# PSU.net
KiCad netlist of a schematic drawn in EAGLE
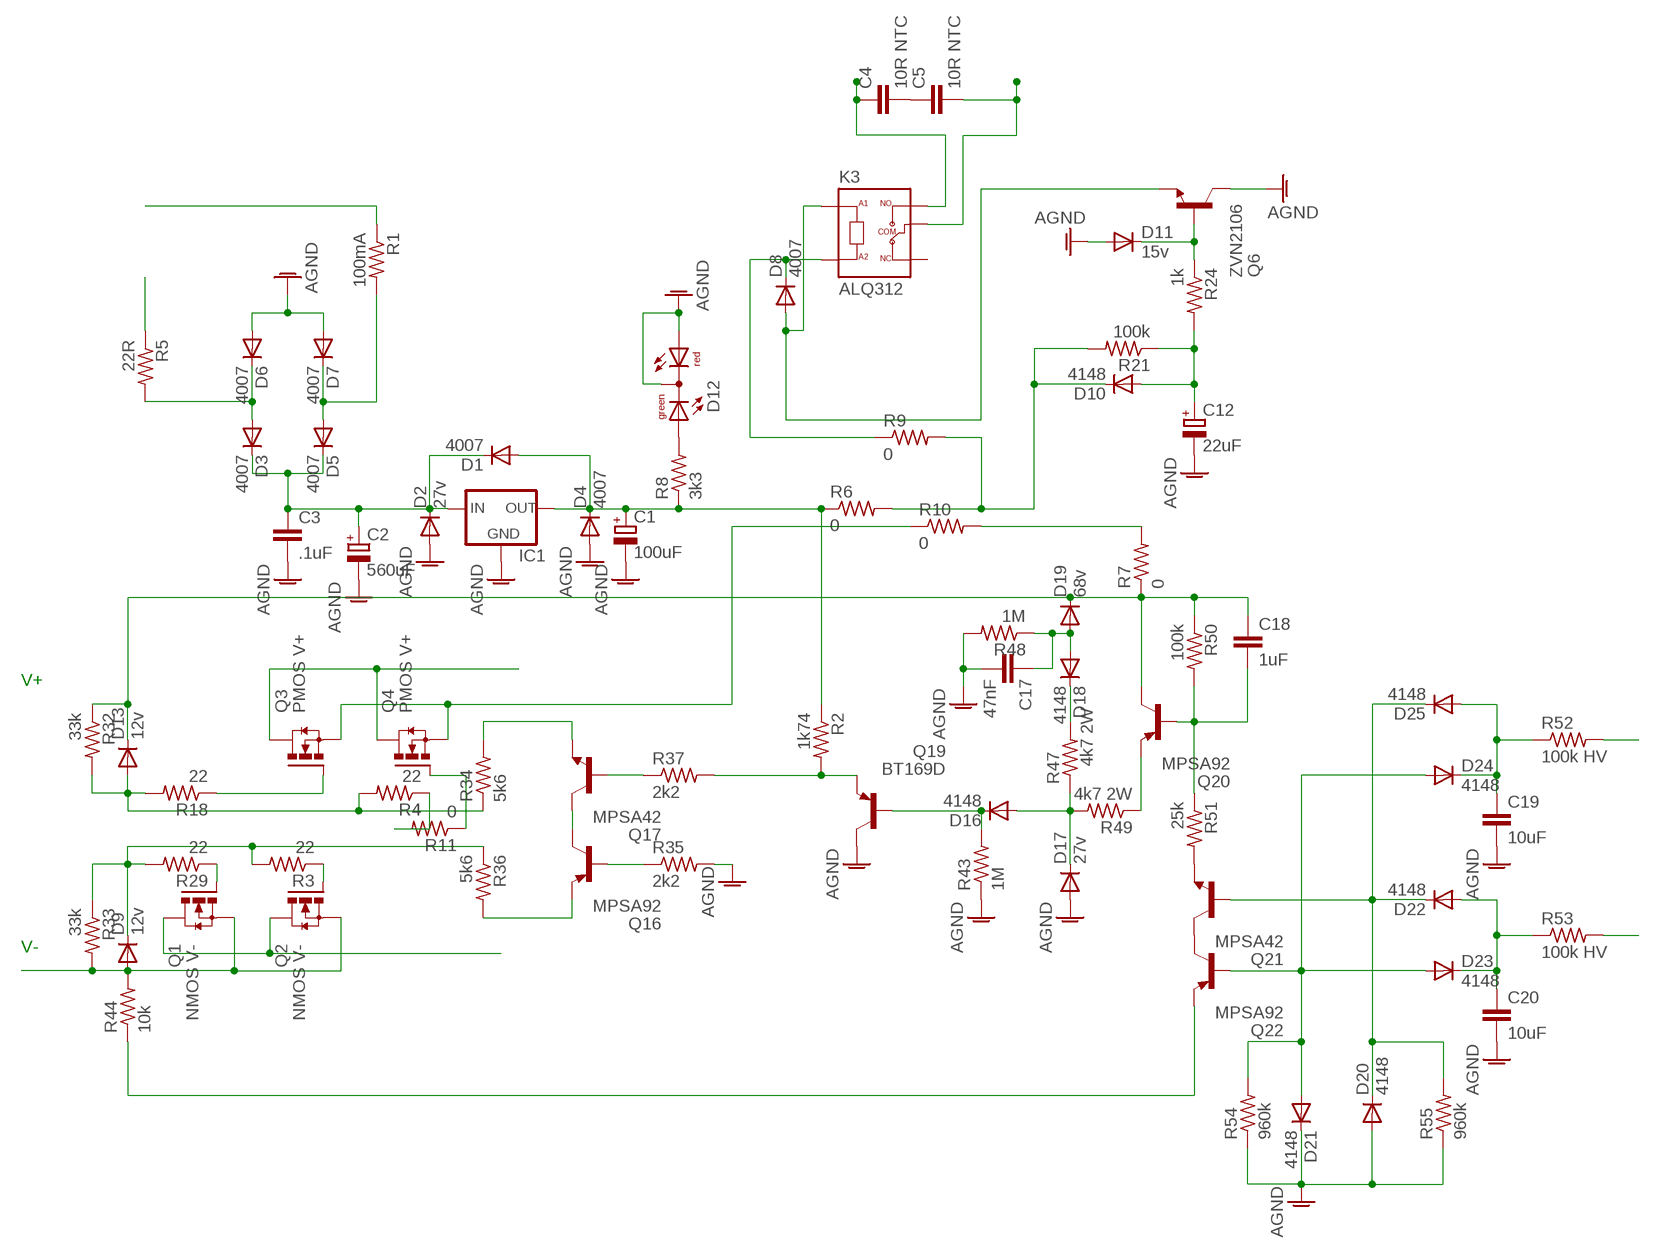
[diagram p0: schematic, sheet 1]

(export (version "E")
  (design (tool "Eeschema 10.0.6"))
  (components
    (comp (ref "C1")
      (value "100uF")
      (footprint "eagle-import:E3,5-10")
      (libsource (lib "eagle-import") (part "CPOL-EUE3.5-10"))
    )
    (comp (ref "C2")
      (value "560uF")
      (footprint "eagle-import:E5-13")
      (libsource (lib "eagle-import") (part "CPOL-EUE5-13"))
    )
    (comp (ref "C3")
      (value ".1uF")
      (footprint "eagle-import:C075-032X103")
      (libsource (lib "eagle-import") (part "C-EU075-032X103"))
    )
    (comp (ref "C4")
      (value "10R NTC")
      (footprint "eagle-import:C075-063X106")
      (libsource (lib "eagle-import") (part "C-EU075-063X106"))
    )
    (comp (ref "C5")
      (value "10R NTC")
      (footprint "eagle-import:C075-063X106")
      (libsource (lib "eagle-import") (part "C-EU075-063X106"))
    )
    (comp (ref "C12")
      (value "22uF")
      (footprint "eagle-import:E2,5-7")
      (libsource (lib "eagle-import") (part "CPOL-EUE2.5-7"))
    )
    (comp (ref "C17")
      (value "47nF")
      (footprint "eagle-import:C050-035X075")
      (libsource (lib "eagle-import") (part "C-EU050-035X075"))
    )
    (comp (ref "C18")
      (value "1uF")
      (footprint "eagle-import:C050-035X075")
      (libsource (lib "eagle-import") (part "C-EU050-035X075"))
    )
    (comp (ref "C19")
      (value "10uF")
      (footprint "eagle-import:C050-075X075")
      (libsource (lib "eagle-import") (part "C-EU050-075X075"))
    )
    (comp (ref "C20")
      (value "10uF")
      (footprint "eagle-import:C050-075X075")
      (libsource (lib "eagle-import") (part "C-EU050-075X075"))
    )
    (comp (ref "D1")
      (value "4007")
      (footprint "eagle-import:DO41-10")
      (libsource (lib "eagle-import") (part "1N4004"))
    )
    (comp (ref "D2")
      (value "27v")
      (footprint "eagle-import:DO41-10")
      (libsource (lib "eagle-import") (part "1N4004"))
    )
    (comp (ref "D3")
      (value "4007")
      (footprint "eagle-import:DO41-10")
      (libsource (lib "eagle-import") (part "1N4004"))
    )
    (comp (ref "D4")
      (value "4007")
      (footprint "eagle-import:DO41-10")
      (libsource (lib "eagle-import") (part "1N4004"))
    )
    (comp (ref "D5")
      (value "4007")
      (footprint "eagle-import:DO41-10")
      (libsource (lib "eagle-import") (part "1N4004"))
    )
    (comp (ref "D6")
      (value "4007")
      (footprint "eagle-import:DO41-10")
      (libsource (lib "eagle-import") (part "1N4004"))
    )
    (comp (ref "D7")
      (value "4007")
      (footprint "eagle-import:DO41-10")
      (libsource (lib "eagle-import") (part "1N4004"))
    )
    (comp (ref "D8")
      (value "4007")
      (footprint "eagle-import:DO41-10")
      (libsource (lib "eagle-import") (part "1N4004"))
    )
    (comp (ref "D9")
      (value "12v")
      (footprint "eagle-import:DO41-10")
      (libsource (lib "eagle-import") (part "1N4004"))
    )
    (comp (ref "D10")
      (value "4148")
      (footprint "eagle-import:DO35-10")
      (libsource (lib "eagle-import") (part "1N4148DO35-10"))
    )
    (comp (ref "D11")
      (value "15v")
      (footprint "eagle-import:DO35-7")
      (libsource (lib "eagle-import") (part "1N4148DO35-7"))
    )
    (comp (ref "D12")
      (value "DUOLED5MM")
      (footprint "eagle-import:DUOLED5MM")
      (libsource (lib "eagle-import") (part "DUOLED5MM"))
    )
    (comp (ref "D13")
      (value "12v")
      (footprint "eagle-import:DO41-10")
      (libsource (lib "eagle-import") (part "1N4004"))
    )
    (comp (ref "D16")
      (value "4148")
      (footprint "eagle-import:DO41-10")
      (libsource (lib "eagle-import") (part "1N4004"))
    )
    (comp (ref "D17")
      (value "27v")
      (footprint "eagle-import:DO41-10")
      (libsource (lib "eagle-import") (part "1N4004"))
    )
    (comp (ref "D18")
      (value "4148")
      (footprint "eagle-import:DO41-10")
      (libsource (lib "eagle-import") (part "1N4004"))
    )
    (comp (ref "D19")
      (value "68v")
      (footprint "eagle-import:DO41-10")
      (libsource (lib "eagle-import") (part "1N4004"))
    )
    (comp (ref "D20")
      (value "4148")
      (footprint "eagle-import:DO35-7")
      (libsource (lib "eagle-import") (part "1N4148DO35-7"))
    )
    (comp (ref "D21")
      (value "4148")
      (footprint "eagle-import:DO35-7")
      (libsource (lib "eagle-import") (part "1N4148DO35-7"))
    )
    (comp (ref "D22")
      (value "4148")
      (footprint "eagle-import:DO35-7")
      (libsource (lib "eagle-import") (part "1N4148DO35-7"))
    )
    (comp (ref "D23")
      (value "4148")
      (footprint "eagle-import:DO35-7")
      (libsource (lib "eagle-import") (part "1N4148DO35-7"))
    )
    (comp (ref "D24")
      (value "4148")
      (footprint "eagle-import:DO35-7")
      (libsource (lib "eagle-import") (part "1N4148DO35-7"))
    )
    (comp (ref "D25")
      (value "4148")
      (footprint "eagle-import:DO35-7")
      (libsource (lib "eagle-import") (part "1N4148DO35-7"))
    )
    (comp (ref "IC1")
      (value "78XXS")
      (footprint "eagle-import:78XXS")
      (libsource (lib "eagle-import") (part "78XXS"))
    )
    (comp (ref "K3")
      (value "ALQ312")
      (footprint "eagle-import:RELAY_ALQ112")
      (fields (field (name "MF") "Panasonic Electric") (field (name "MP") "ALQ112"))
      (libsource (lib "eagle-import") (part "ALQ112"))
    )
    (comp (ref "Q1")
      (value "NMOS V-")
      (footprint "eagle-import:TO247BV")
      (libsource (lib "eagle-import") (part "IRFP240"))
    )
    (comp (ref "Q2")
      (value "NMOS V-")
      (footprint "eagle-import:TO247BV")
      (libsource (lib "eagle-import") (part "IRFP240"))
    )
    (comp (ref "Q3")
      (value "PMOS V+")
      (footprint "eagle-import:TO247BV")
      (libsource (lib "eagle-import") (part "IRFP240"))
    )
    (comp (ref "Q4")
      (value "PMOS V+")
      (footprint "eagle-import:TO247BV")
      (libsource (lib "eagle-import") (part "IRFP240"))
    )
    (comp (ref "Q6")
      (value "ZVN2106")
      (footprint "eagle-import:TO92-EBC")
      (libsource (lib "eagle-import") (part "BC550B"))
    )
    (comp (ref "Q16")
      (value "MPSA92")
      (footprint "eagle-import:TO92-EBC")
      (libsource (lib "eagle-import") (part "BC560"))
    )
    (comp (ref "Q17")
      (value "MPSA42")
      (footprint "eagle-import:TO92-EBC")
      (libsource (lib "eagle-import") (part "BC550B"))
    )
    (comp (ref "Q19")
      (value "BT169D")
      (footprint "eagle-import:TO92-EBC")
      (libsource (lib "eagle-import") (part "BC560"))
    )
    (comp (ref "Q20")
      (value "MPSA92")
      (footprint "eagle-import:TO92-EBC")
      (libsource (lib "eagle-import") (part "BC560"))
    )
    (comp (ref "Q21")
      (value "MPSA42")
      (footprint "eagle-import:TO92-EBC")
      (libsource (lib "eagle-import") (part "BC550B"))
    )
    (comp (ref "Q22")
      (value "MPSA92")
      (footprint "eagle-import:TO92-EBC")
      (libsource (lib "eagle-import") (part "BC560"))
    )
    (comp (ref "R1")
      (value "100mA")
      (footprint "eagle-import:0207_5V")
      (libsource (lib "eagle-import") (part "R-US_0207/5V"))
    )
    (comp (ref "R2")
      (value "1k74")
      (footprint "eagle-import:0309_10")
      (libsource (lib "eagle-import") (part "R-US_0309/10"))
    )
    (comp (ref "R3")
      (value "22")
      (footprint "eagle-import:0309_12")
      (libsource (lib "eagle-import") (part "R-US_0309/12"))
    )
    (comp (ref "R4")
      (value "22")
      (footprint "eagle-import:0309_12")
      (libsource (lib "eagle-import") (part "R-US_0309/12"))
    )
    (comp (ref "R5")
      (value "22R")
      (footprint "eagle-import:0309_12")
      (libsource (lib "eagle-import") (part "R-US_0309/12"))
    )
    (comp (ref "R6")
      (value "0")
      (footprint "eagle-import:0309_12")
      (libsource (lib "eagle-import") (part "R-US_0309/12"))
    )
    (comp (ref "R7")
      (value "0")
      (footprint "eagle-import:0309_12")
      (libsource (lib "eagle-import") (part "R-US_0309/12"))
    )
    (comp (ref "R8")
      (value "3k3")
      (footprint "eagle-import:0309_10")
      (libsource (lib "eagle-import") (part "R-US_0309/10"))
    )
    (comp (ref "R9")
      (value "0")
      (footprint "eagle-import:0309_10")
      (libsource (lib "eagle-import") (part "R-US_0309/10"))
    )
    (comp (ref "R10")
      (value "0")
      (footprint "eagle-import:0309_12")
      (libsource (lib "eagle-import") (part "R-US_0309/12"))
    )
    (comp (ref "R11")
      (value "0")
      (footprint "eagle-import:0309_12")
      (libsource (lib "eagle-import") (part "R-US_0309/12"))
    )
    (comp (ref "R18")
      (value "22")
      (footprint "eagle-import:0207_15")
      (libsource (lib "eagle-import") (part "R-US_0207/15"))
    )
    (comp (ref "R21")
      (value "100k")
      (footprint "eagle-import:0309_10")
      (libsource (lib "eagle-import") (part "R-US_0309/10"))
    )
    (comp (ref "R24")
      (value "1k")
      (footprint "eagle-import:0309_10")
      (libsource (lib "eagle-import") (part "R-US_0309/10"))
    )
    (comp (ref "R29")
      (value "22")
      (footprint "eagle-import:0207_15")
      (libsource (lib "eagle-import") (part "R-US_0207/15"))
    )
    (comp (ref "R32")
      (value "33k")
      (footprint "eagle-import:0411_15")
      (libsource (lib "eagle-import") (part "R-US_0411/15"))
    )
    (comp (ref "R33")
      (value "33k")
      (footprint "eagle-import:0411_15")
      (libsource (lib "eagle-import") (part "R-US_0411/15"))
    )
    (comp (ref "R34")
      (value "5k6")
      (footprint "eagle-import:0411_15")
      (libsource (lib "eagle-import") (part "R-US_0411/15"))
    )
    (comp (ref "R35")
      (value "2k2")
      (footprint "eagle-import:0309_10")
      (libsource (lib "eagle-import") (part "R-US_0309/10"))
    )
    (comp (ref "R36")
      (value "5k6")
      (footprint "eagle-import:0411_15")
      (libsource (lib "eagle-import") (part "R-US_0411/15"))
    )
    (comp (ref "R37")
      (value "2k2")
      (footprint "eagle-import:0309_10")
      (libsource (lib "eagle-import") (part "R-US_0309/10"))
    )
    (comp (ref "R43")
      (value "1M")
      (footprint "eagle-import:0309_10")
      (libsource (lib "eagle-import") (part "R-US_0309/10"))
    )
    (comp (ref "R44")
      (value "10k")
      (footprint "eagle-import:0411_15")
      (libsource (lib "eagle-import") (part "R-US_0411/15"))
    )
    (comp (ref "R47")
      (value "4k7 2W")
      (footprint "eagle-import:0309_10")
      (libsource (lib "eagle-import") (part "R-US_0309/10"))
    )
    (comp (ref "R48")
      (value "1M")
      (footprint "eagle-import:0411_15")
      (libsource (lib "eagle-import") (part "R-US_0411/15"))
    )
    (comp (ref "R49")
      (value "4k7 2W")
      (footprint "eagle-import:0309_10")
      (libsource (lib "eagle-import") (part "R-US_0309/10"))
    )
    (comp (ref "R50")
      (value "100k")
      (footprint "eagle-import:0309_10")
      (libsource (lib "eagle-import") (part "R-US_0309/10"))
    )
    (comp (ref "R51")
      (value "25k")
      (footprint "eagle-import:0309_10")
      (libsource (lib "eagle-import") (part "R-US_0309/10"))
    )
    (comp (ref "R52")
      (value "100k HV")
      (footprint "eagle-import:0309_12")
      (libsource (lib "eagle-import") (part "R-US_0309/12"))
    )
    (comp (ref "R53")
      (value "100k HV")
      (footprint "eagle-import:0309_12")
      (libsource (lib "eagle-import") (part "R-US_0309/12"))
    )
    (comp (ref "R54")
      (value "960k")
      (footprint "eagle-import:0309_10")
      (libsource (lib "eagle-import") (part "R-US_0309/10"))
    )
    (comp (ref "R55")
      (value "960k")
      (footprint "eagle-import:0309_10")
      (libsource (lib "eagle-import") (part "R-US_0309/10"))
    )
  )
  (nets
    (net (code "1") (name "AGND") (class "Default")
      (node (ref "C1") (pin "-") (pinfunction "-_-") (pintype "passive"))
      (node (ref "C12") (pin "-") (pinfunction "-_-") (pintype "passive"))
      (node (ref "C17") (pin "2") (pinfunction "2_2") (pintype "passive"))
      (node (ref "C19") (pin "2") (pinfunction "2_2") (pintype "passive"))
      (node (ref "C2") (pin "-") (pinfunction "-_-") (pintype "passive"))
      (node (ref "C20") (pin "2") (pinfunction "2_2") (pintype "passive"))
      (node (ref "C3") (pin "2") (pinfunction "2_2") (pintype "passive"))
      (node (ref "D11") (pin "A") (pinfunction "A_A") (pintype "passive"))
      (node (ref "D12") (pin "AR") (pinfunction "AR_AR") (pintype "passive"))
      (node (ref "D12") (pin "K") (pinfunction "C_K") (pintype "passive"))
      (node (ref "D17") (pin "A") (pinfunction "A_A") (pintype "passive"))
      (node (ref "D2") (pin "A") (pinfunction "A_A") (pintype "passive"))
      (node (ref "D20") (pin "A") (pinfunction "A_A") (pintype "passive"))
      (node (ref "D21") (pin "C") (pinfunction "C_C") (pintype "passive"))
      (node (ref "D4") (pin "A") (pinfunction "A_A") (pintype "passive"))
      (node (ref "D6") (pin "A") (pinfunction "A_A") (pintype "passive"))
      (node (ref "D7") (pin "A") (pinfunction "A_A") (pintype "passive"))
      (node (ref "IC1") (pin "GND") (pinfunction "GND_GND") (pintype "input"))
      (node (ref "Q19") (pin "C") (pinfunction "C_C") (pintype "passive"))
      (node (ref "Q6") (pin "C") (pinfunction "C_C") (pintype "passive"))
      (node (ref "R35") (pin "2") (pinfunction "2_2") (pintype "passive"))
      (node (ref "R43") (pin "1") (pinfunction "1_1") (pintype "passive"))
      (node (ref "R48") (pin "2") (pinfunction "2_2") (pintype "passive"))
      (node (ref "R54") (pin "1") (pinfunction "1_1") (pintype "passive"))
      (node (ref "R55") (pin "1") (pinfunction "1_1") (pintype "passive"))
    )
    (net (code "2") (name "Net-(C1-Pad+)") (class "Default")
      (node (ref "C1") (pin "+") (pinfunction "+_+") (pintype "passive"))
      (node (ref "D1") (pin "A") (pinfunction "A_A") (pintype "passive"))
      (node (ref "D4") (pin "C") (pinfunction "C_C") (pintype "passive"))
      (node (ref "IC1") (pin "OUT") (pinfunction "OUT_OUT") (pintype "passive"))
      (node (ref "R2") (pin "1") (pinfunction "1_1") (pintype "passive"))
      (node (ref "R6") (pin "1") (pinfunction "1_1") (pintype "passive"))
      (node (ref "R8") (pin "1") (pinfunction "1_1") (pintype "passive"))
    )
    (net (code "3") (name "Net-(C2-Pad+)") (class "Default")
      (node (ref "C2") (pin "+") (pinfunction "+_+") (pintype "passive"))
      (node (ref "C3") (pin "1") (pinfunction "1_1") (pintype "passive"))
      (node (ref "D1") (pin "C") (pinfunction "C_C") (pintype "passive"))
      (node (ref "D2") (pin "C") (pinfunction "C_C") (pintype "passive"))
      (node (ref "D3") (pin "C") (pinfunction "C_C") (pintype "passive"))
      (node (ref "D5") (pin "C") (pinfunction "C_C") (pintype "passive"))
      (node (ref "IC1") (pin "IN") (pinfunction "IN_IN") (pintype "input"))
    )
    (net (code "4") (name "Net-(C4-Pad2)") (class "Default")
      (node (ref "C4") (pin "2") (pinfunction "2_2") (pintype "passive"))
      (node (ref "C5") (pin "1") (pinfunction "1_1") (pintype "passive"))
    )
    (net (code "5") (name "Net-(C12-Pad+)") (class "Default")
      (node (ref "C12") (pin "+") (pinfunction "+_+") (pintype "passive"))
      (node (ref "D10") (pin "A") (pinfunction "A_A") (pintype "passive"))
      (node (ref "R21") (pin "1") (pinfunction "1_1") (pintype "passive"))
      (node (ref "R24") (pin "2") (pinfunction "2_2") (pintype "passive"))
    )
    (net (code "6") (name "Net-(C17-Pad1)") (class "Default")
      (node (ref "C17") (pin "1") (pinfunction "1_1") (pintype "passive"))
      (node (ref "D18") (pin "A") (pinfunction "A_A") (pintype "passive"))
      (node (ref "D19") (pin "A") (pinfunction "A_A") (pintype "passive"))
      (node (ref "R48") (pin "1") (pinfunction "1_1") (pintype "passive"))
    )
    (net (code "7") (name "Net-(C18-Pad1)") (class "Default")
      (node (ref "C18") (pin "1") (pinfunction "1_1") (pintype "passive"))
      (node (ref "D13") (pin "C") (pinfunction "C_C") (pintype "passive"))
      (node (ref "D19") (pin "C") (pinfunction "C_C") (pintype "passive"))
      (node (ref "Q20") (pin "C") (pinfunction "C_C") (pintype "passive"))
      (node (ref "R32") (pin "1") (pinfunction "1_1") (pintype "passive"))
      (node (ref "R50") (pin "1") (pinfunction "1_1") (pintype "passive"))
      (node (ref "R7") (pin "1") (pinfunction "1_1") (pintype "passive"))
    )
    (net (code "8") (name "Net-(C18-Pad2)") (class "Default")
      (node (ref "C18") (pin "2") (pinfunction "2_2") (pintype "passive"))
      (node (ref "Q20") (pin "B") (pinfunction "B_B") (pintype "passive"))
      (node (ref "R50") (pin "2") (pinfunction "2_2") (pintype "passive"))
      (node (ref "R51") (pin "1") (pinfunction "1_1") (pintype "passive"))
    )
    (net (code "9") (name "Net-(C19-Pad1)") (class "Default")
      (node (ref "C19") (pin "1") (pinfunction "1_1") (pintype "passive"))
      (node (ref "D24") (pin "C") (pinfunction "C_C") (pintype "passive"))
      (node (ref "D25") (pin "A") (pinfunction "A_A") (pintype "passive"))
      (node (ref "R52") (pin "1") (pinfunction "1_1") (pintype "passive"))
    )
    (net (code "10") (name "Net-(C20-Pad1)") (class "Default")
      (node (ref "C20") (pin "1") (pinfunction "1_1") (pintype "passive"))
      (node (ref "D22") (pin "A") (pinfunction "A_A") (pintype "passive"))
      (node (ref "D23") (pin "C") (pinfunction "C_C") (pintype "passive"))
      (node (ref "R53") (pin "1") (pinfunction "1_1") (pintype "passive"))
    )
    (net (code "11") (name "Net-(D3-PadA)") (class "Default")
      (node (ref "D3") (pin "A") (pinfunction "A_A") (pintype "passive"))
      (node (ref "D6") (pin "C") (pinfunction "C_C") (pintype "passive"))
      (node (ref "R5") (pin "2") (pinfunction "2_2") (pintype "passive"))
    )
    (net (code "12") (name "Net-(D5-PadA)") (class "Default")
      (node (ref "D5") (pin "A") (pinfunction "A_A") (pintype "passive"))
      (node (ref "D7") (pin "C") (pinfunction "C_C") (pintype "passive"))
      (node (ref "R1") (pin "2") (pinfunction "2_2") (pintype "passive"))
    )
    (net (code "13") (name "Net-(D9-PadA)") (class "Default")
      (node (ref "D9") (pin "A") (pinfunction "A_A") (pintype "passive"))
      (node (ref "Q1") (pin "S") (pinfunction "S_S") (pintype "passive"))
      (node (ref "Q2") (pin "S") (pinfunction "S_S") (pintype "passive"))
      (node (ref "R33") (pin "2") (pinfunction "2_2") (pintype "passive"))
      (node (ref "R44") (pin "2") (pinfunction "2_2") (pintype "passive"))
    )
    (net (code "14") (name "Net-(D9-PadC)") (class "Default")
      (node (ref "D9") (pin "C") (pinfunction "C_C") (pintype "passive"))
      (node (ref "R29") (pin "2") (pinfunction "2_2") (pintype "passive"))
      (node (ref "R3") (pin "2") (pinfunction "2_2") (pintype "passive"))
      (node (ref "R33") (pin "1") (pinfunction "1_1") (pintype "passive"))
      (node (ref "R36") (pin "1") (pinfunction "1_1") (pintype "passive"))
    )
    (net (code "15") (name "Net-(D10-PadC)") (class "Default")
      (node (ref "D10") (pin "C") (pinfunction "C_C") (pintype "passive"))
      (node (ref "R21") (pin "2") (pinfunction "2_2") (pintype "passive"))
      (node (ref "R6") (pin "2") (pinfunction "2_2") (pintype "passive"))
      (node (ref "R9") (pin "2") (pinfunction "2_2") (pintype "passive"))
    )
    (net (code "16") (name "Net-(D11-PadC)") (class "Default")
      (node (ref "D11") (pin "C") (pinfunction "C_C") (pintype "passive"))
      (node (ref "Q6") (pin "B") (pinfunction "B_B") (pintype "passive"))
      (node (ref "R24") (pin "1") (pinfunction "1_1") (pintype "passive"))
    )
    (net (code "17") (name "Net-(D12-PadAG)") (class "Default")
      (node (ref "D12") (pin "AG") (pinfunction "AG_AG") (pintype "passive"))
      (node (ref "R8") (pin "2") (pinfunction "2_2") (pintype "passive"))
    )
    (net (code "18") (name "Net-(D13-PadA)") (class "Default")
      (node (ref "D13") (pin "A") (pinfunction "A_A") (pintype "passive"))
      (node (ref "R18") (pin "2") (pinfunction "2_2") (pintype "passive"))
      (node (ref "R32") (pin "2") (pinfunction "2_2") (pintype "passive"))
      (node (ref "R34") (pin "1") (pinfunction "1_1") (pintype "passive"))
      (node (ref "R4") (pin "2") (pinfunction "2_2") (pintype "passive"))
    )
    (net (code "19") (name "Net-(D16-PadA)") (class "Default")
      (node (ref "D16") (pin "A") (pinfunction "A_A") (pintype "passive"))
      (node (ref "D17") (pin "C") (pinfunction "C_C") (pintype "passive"))
      (node (ref "R47") (pin "1") (pinfunction "1_1") (pintype "passive"))
      (node (ref "R49") (pin "2") (pinfunction "2_2") (pintype "passive"))
    )
    (net (code "20") (name "Net-(D16-PadC)") (class "Default")
      (node (ref "D16") (pin "C") (pinfunction "C_C") (pintype "passive"))
      (node (ref "Q19") (pin "B") (pinfunction "B_B") (pintype "passive"))
      (node (ref "R43") (pin "2") (pinfunction "2_2") (pintype "passive"))
    )
    (net (code "21") (name "Net-(D18-PadC)") (class "Default")
      (node (ref "D18") (pin "C") (pinfunction "C_C") (pintype "passive"))
      (node (ref "R47") (pin "2") (pinfunction "2_2") (pintype "passive"))
    )
    (net (code "22") (name "Net-(D20-PadC)") (class "Default")
      (node (ref "D20") (pin "C") (pinfunction "C_C") (pintype "passive"))
      (node (ref "D22") (pin "C") (pinfunction "C_C") (pintype "passive"))
      (node (ref "D25") (pin "C") (pinfunction "C_C") (pintype "passive"))
      (node (ref "Q21") (pin "B") (pinfunction "B_B") (pintype "passive"))
      (node (ref "R55") (pin "2") (pinfunction "2_2") (pintype "passive"))
    )
    (net (code "23") (name "Net-(D21-PadA)") (class "Default")
      (node (ref "D21") (pin "A") (pinfunction "A_A") (pintype "passive"))
      (node (ref "D23") (pin "A") (pinfunction "A_A") (pintype "passive"))
      (node (ref "D24") (pin "A") (pinfunction "A_A") (pintype "passive"))
      (node (ref "Q22") (pin "B") (pinfunction "B_B") (pintype "passive"))
      (node (ref "R54") (pin "2") (pinfunction "2_2") (pintype "passive"))
    )
    (net (code "24") (name "Net-(K3-A1)") (class "Default")
      (node (ref "D8") (pin "A") (pinfunction "A_A") (pintype "passive"))
      (node (ref "K3") (pin "1") (pinfunction "A1_1") (pintype "passive"))
      (node (ref "Q6") (pin "E") (pinfunction "E_E") (pintype "passive"))
    )
    (net (code "25") (name "Net-(K3-A2)") (class "Default")
      (node (ref "D8") (pin "C") (pinfunction "C_C") (pintype "passive"))
      (node (ref "K3") (pin "2") (pinfunction "A2_2") (pintype "passive"))
      (node (ref "R9") (pin "1") (pinfunction "1_1") (pintype "passive"))
    )
    (net (code "26") (name "Net-(K3-COM)") (class "Default")
      (node (ref "C5") (pin "2") (pinfunction "2_2") (pintype "passive"))
      (node (ref "K3") (pin "3") (pinfunction "COM_3") (pintype "passive"))
    )
    (net (code "27") (name "Net-(K3-NO)") (class "Default")
      (node (ref "C4") (pin "1") (pinfunction "1_1") (pintype "passive"))
      (node (ref "K3") (pin "5") (pinfunction "NO_5") (pintype "passive"))
    )
    (net (code "28") (name "Net-(Q1-PadD)") (class "Default")
      (node (ref "Q1") (pin "D") (pinfunction "D_D") (pintype "passive"))
      (node (ref "Q2") (pin "D") (pinfunction "D_D") (pintype "passive"))
    )
    (net (code "29") (name "Net-(Q1-PadG)") (class "Default")
      (node (ref "Q1") (pin "G") (pinfunction "G_G") (pintype "passive"))
      (node (ref "R29") (pin "1") (pinfunction "1_1") (pintype "passive"))
    )
    (net (code "30") (name "Net-(Q2-PadG)") (class "Default")
      (node (ref "Q2") (pin "G") (pinfunction "G_G") (pintype "passive"))
      (node (ref "R3") (pin "1") (pinfunction "1_1") (pintype "passive"))
    )
    (net (code "31") (name "Net-(Q3-PadD)") (class "Default")
      (node (ref "Q3") (pin "D") (pinfunction "D_D") (pintype "passive"))
      (node (ref "Q4") (pin "D") (pinfunction "D_D") (pintype "passive"))
    )
    (net (code "32") (name "Net-(Q3-PadG)") (class "Default")
      (node (ref "Q3") (pin "G") (pinfunction "G_G") (pintype "passive"))
      (node (ref "R18") (pin "1") (pinfunction "1_1") (pintype "passive"))
    )
    (net (code "33") (name "Net-(Q3-PadS)") (class "Default")
      (node (ref "Q3") (pin "S") (pinfunction "S_S") (pintype "passive"))
      (node (ref "Q4") (pin "S") (pinfunction "S_S") (pintype "passive"))
      (node (ref "R10") (pin "1") (pinfunction "1_1") (pintype "passive"))
    )
    (net (code "34") (name "Net-(Q4-PadG)") (class "Default")
      (node (ref "Q4") (pin "G") (pinfunction "G_G") (pintype "passive"))
      (node (ref "R11") (pin "1") (pinfunction "1_1") (pintype "passive"))
    )
    (net (code "35") (name "Net-(Q16-PadB)") (class "Default")
      (node (ref "Q16") (pin "B") (pinfunction "B_B") (pintype "passive"))
      (node (ref "R35") (pin "1") (pinfunction "1_1") (pintype "passive"))
    )
    (net (code "36") (name "Net-(Q16-PadC)") (class "Default")
      (node (ref "Q16") (pin "C") (pinfunction "C_C") (pintype "passive"))
      (node (ref "Q17") (pin "C") (pinfunction "C_C") (pintype "passive"))
    )
    (net (code "37") (name "Net-(Q16-PadE)") (class "Default")
      (node (ref "Q16") (pin "E") (pinfunction "E_E") (pintype "passive"))
      (node (ref "R36") (pin "2") (pinfunction "2_2") (pintype "passive"))
    )
    (net (code "38") (name "Net-(Q17-PadB)") (class "Default")
      (node (ref "Q17") (pin "B") (pinfunction "B_B") (pintype "passive"))
      (node (ref "R37") (pin "1") (pinfunction "1_1") (pintype "passive"))
    )
    (net (code "39") (name "Net-(Q17-PadE)") (class "Default")
      (node (ref "Q17") (pin "E") (pinfunction "E_E") (pintype "passive"))
      (node (ref "R34") (pin "2") (pinfunction "2_2") (pintype "passive"))
    )
    (net (code "40") (name "Net-(Q19-PadE)") (class "Default")
      (node (ref "Q19") (pin "E") (pinfunction "E_E") (pintype "passive"))
      (node (ref "R2") (pin "2") (pinfunction "2_2") (pintype "passive"))
      (node (ref "R37") (pin "2") (pinfunction "2_2") (pintype "passive"))
    )
    (net (code "41") (name "Net-(Q20-PadE)") (class "Default")
      (node (ref "Q20") (pin "E") (pinfunction "E_E") (pintype "passive"))
      (node (ref "R49") (pin "1") (pinfunction "1_1") (pintype "passive"))
    )
    (net (code "42") (name "Net-(Q21-PadC)") (class "Default")
      (node (ref "Q21") (pin "C") (pinfunction "C_C") (pintype "passive"))
      (node (ref "Q22") (pin "C") (pinfunction "C_C") (pintype "passive"))
    )
    (net (code "43") (name "Net-(Q21-PadE)") (class "Default")
      (node (ref "Q21") (pin "E") (pinfunction "E_E") (pintype "passive"))
      (node (ref "R51") (pin "2") (pinfunction "2_2") (pintype "passive"))
    )
    (net (code "44") (name "Net-(Q22-PadE)") (class "Default")
      (node (ref "Q22") (pin "E") (pinfunction "E_E") (pintype "passive"))
      (node (ref "R44") (pin "1") (pinfunction "1_1") (pintype "passive"))
    )
    (net (code "45") (name "Net-(R10-Pad2)") (class "Default")
      (node (ref "R10") (pin "2") (pinfunction "2_2") (pintype "passive"))
      (node (ref "R7") (pin "2") (pinfunction "2_2") (pintype "passive"))
    )
    (net (code "46") (name "Net-(R11-Pad2)") (class "Default")
      (node (ref "R11") (pin "2") (pinfunction "2_2") (pintype "passive"))
      (node (ref "R4") (pin "1") (pinfunction "1_1") (pintype "passive"))
    )
    (net (code "47") (name "unconnected-(K3-NC-Pad4)") (class "Default")
      (node (ref "K3") (pin "4") (pinfunction "NC_4") (pintype "passive"))
    )
    (net (code "48") (name "unconnected-(R1-Pad1)") (class "Default")
      (node (ref "R1") (pin "1") (pinfunction "1_1") (pintype "passive"))
    )
    (net (code "49") (name "unconnected-(R5-Pad1)") (class "Default")
      (node (ref "R5") (pin "1") (pinfunction "1_1") (pintype "passive"))
    )
    (net (code "50") (name "unconnected-(R52-Pad2)") (class "Default")
      (node (ref "R52") (pin "2") (pinfunction "2_2") (pintype "passive"))
    )
    (net (code "51") (name "unconnected-(R53-Pad2)") (class "Default")
      (node (ref "R53") (pin "2") (pinfunction "2_2") (pintype "passive"))
    )
  )
)
